# MAIN.net
KiCad netlist of a schematic drawn in Altium Designer
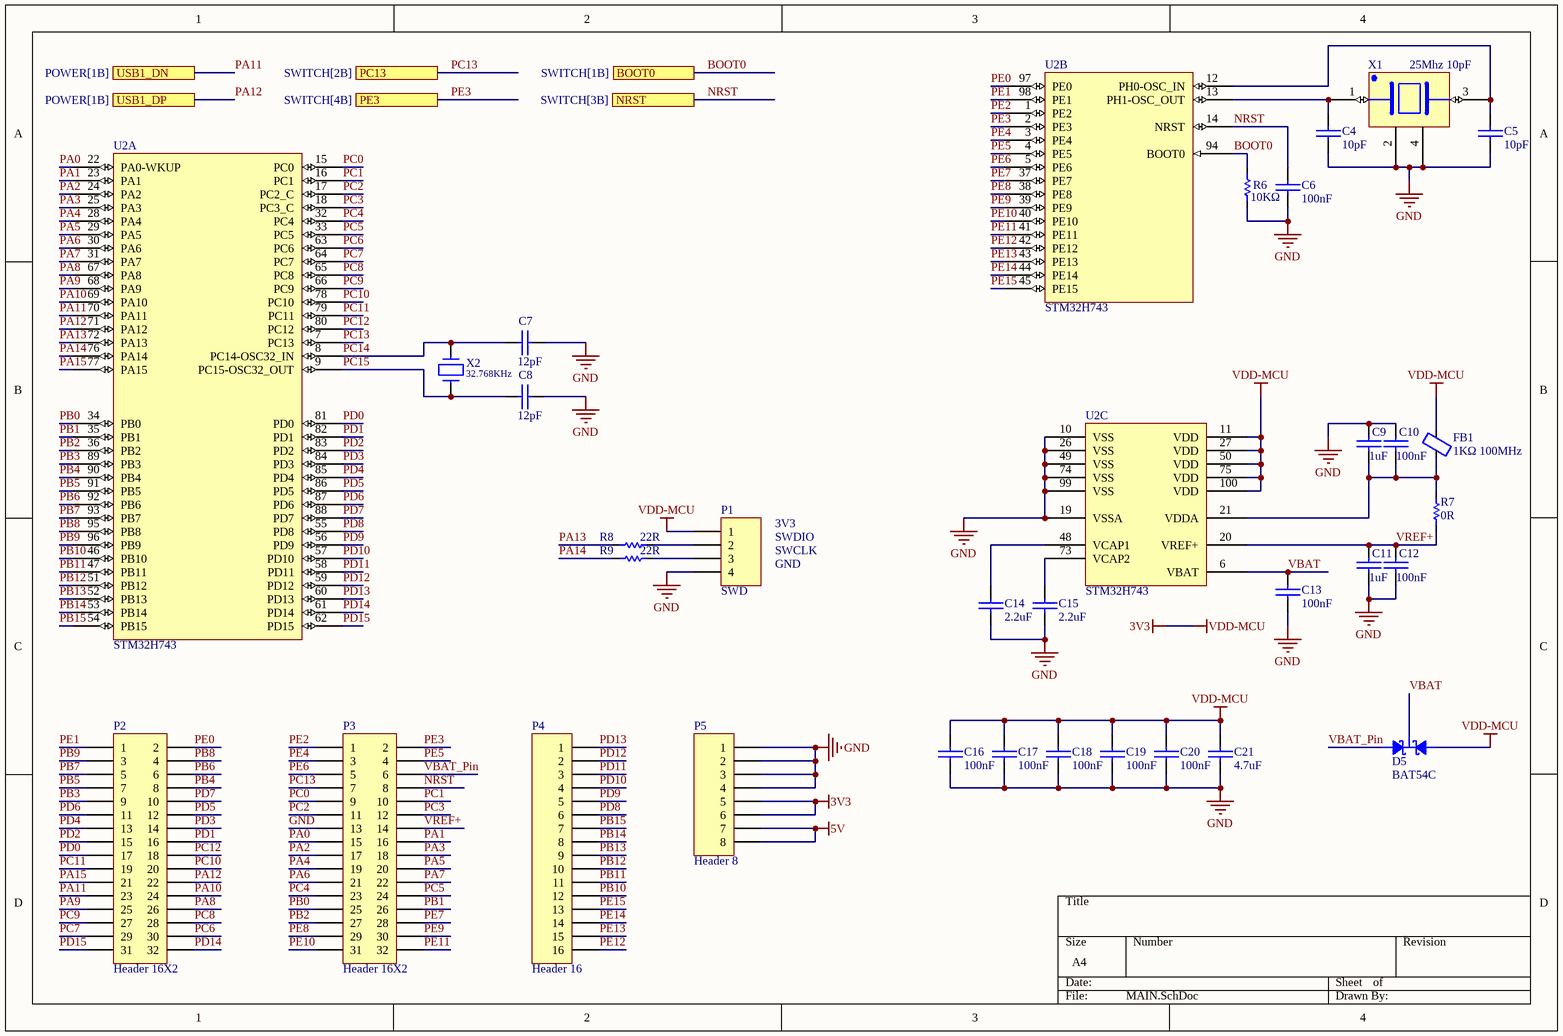
[diagram p0: MAIN.SchDoc]

(export (version "E")
  (design (tool "Eeschema 10.0.6"))
  (components
    (comp (ref "C4")
      (value "10pF")
      (footprint "0402_Capacitor")
      (description "SMDCapacitor")
      (libsource (lib "Miscellaneous Devices-KST") (part "CAP-Chip"))
    )
    (comp (ref "C5")
      (value "10pF")
      (footprint "0402_Capacitor")
      (description "SMDCapacitor")
      (libsource (lib "Miscellaneous Devices-KST") (part "CAP-Chip"))
    )
    (comp (ref "C6")
      (value "100nF")
      (footprint "0402_Capacitor")
      (description "SMDCapacitor")
      (libsource (lib "Miscellaneous Devices-KST") (part "CAP-Chip"))
    )
    (comp (ref "C7")
      (value "12pF")
      (footprint "0402_Capacitor")
      (description "SMDCapacitor")
      (libsource (lib "Miscellaneous Devices-KST") (part "CAP-Chip"))
    )
    (comp (ref "C8")
      (value "12pF")
      (footprint "0402_Capacitor")
      (description "SMDCapacitor")
      (libsource (lib "Miscellaneous Devices-KST") (part "CAP-Chip"))
    )
    (comp (ref "C9")
      (value "1uF")
      (footprint "0402_Capacitor")
      (description "SMDCapacitor")
      (libsource (lib "Miscellaneous Devices-KST") (part "CAP-Chip"))
    )
    (comp (ref "C10")
      (value "100nF")
      (footprint "0402_Capacitor")
      (description "SMDCapacitor")
      (libsource (lib "Miscellaneous Devices-KST") (part "CAP-Chip"))
    )
    (comp (ref "C11")
      (value "1uF")
      (footprint "0402_Capacitor")
      (description "SMDCapacitor")
      (libsource (lib "Miscellaneous Devices-KST") (part "CAP-Chip"))
    )
    (comp (ref "C12")
      (value "100nF")
      (footprint "0402_Capacitor")
      (description "SMDCapacitor")
      (libsource (lib "Miscellaneous Devices-KST") (part "CAP-Chip"))
    )
    (comp (ref "C13")
      (value "100nF")
      (footprint "0402_Capacitor")
      (description "SMDCapacitor")
      (libsource (lib "Miscellaneous Devices-KST") (part "CAP-Chip"))
    )
    (comp (ref "C14")
      (value "2.2uF")
      (footprint "0402_Capacitor")
      (description "SMDCapacitor")
      (libsource (lib "Miscellaneous Devices-KST") (part "CAP-Chip"))
    )
    (comp (ref "C15")
      (value "2.2uF")
      (footprint "0402_Capacitor")
      (description "SMDCapacitor")
      (libsource (lib "Miscellaneous Devices-KST") (part "CAP-Chip"))
    )
    (comp (ref "C16")
      (value "100nF")
      (footprint "0402_Capacitor")
      (description "SMDCapacitor")
      (libsource (lib "Miscellaneous Devices-KST") (part "CAP-Chip"))
    )
    (comp (ref "C17")
      (value "100nF")
      (footprint "0402_Capacitor")
      (description "SMDCapacitor")
      (libsource (lib "Miscellaneous Devices-KST") (part "CAP-Chip"))
    )
    (comp (ref "C18")
      (value "100nF")
      (footprint "0402_Capacitor")
      (description "SMDCapacitor")
      (libsource (lib "Miscellaneous Devices-KST") (part "CAP-Chip"))
    )
    (comp (ref "C19")
      (value "100nF")
      (footprint "0402_Capacitor")
      (description "SMDCapacitor")
      (libsource (lib "Miscellaneous Devices-KST") (part "CAP-Chip"))
    )
    (comp (ref "C20")
      (value "100nF")
      (footprint "0402_Capacitor")
      (description "SMDCapacitor")
      (libsource (lib "Miscellaneous Devices-KST") (part "CAP-Chip"))
    )
    (comp (ref "C21")
      (value "4.7uF")
      (footprint "0402_Capacitor")
      (description "SMDCapacitor")
      (libsource (lib "Miscellaneous Devices-KST") (part "CAP-Chip"))
    )
    (comp (ref "D5") (value "BAT54C") (footprint "SOT23_3L") (libsource (lib "STM32H743") (part "BAT54C")))
    (comp (ref "FB1")
      (value "1KΩ 100MHz")
      (footprint "0603_Ferrite_Bead")
      (libsource (lib "STM32H743") (part "FB1"))
    )
    (comp (ref "P1")
      (value "SWD")
      (footprint "SWD")
      (description "Header, 4-Pin, Right Angle")
      (fields (field (name "PUBLISHER") "Altium Limited"))
      (libsource (lib "Miscellaneous Connectors") (part "Header 4H"))
    )
    (comp (ref "P2")
      (value "Header 16X2")
      (footprint "16x2_Header")
      (description "Header, 16-Pin, Dual row")
      (fields (field (name "PUBLISHER") "Altium Limited"))
      (libsource (lib "Miscellaneous Connectors") (part "Header 16X2"))
    )
    (comp (ref "P3")
      (value "Header 16X2")
      (footprint "16x2_Header")
      (description "Header, 16-Pin, Dual row")
      (fields (field (name "PUBLISHER") "Altium Limited"))
      (libsource (lib "Miscellaneous Connectors") (part "Header 16X2"))
    )
    (comp (ref "P4")
      (value "Header 16")
      (footprint "16x1_Header")
      (description "Header, 16-Pin")
      (fields (field (name "PUBLISHER") "Altium Limited"))
      (libsource (lib "Miscellaneous Connectors") (part "Header 16"))
    )
    (comp (ref "P5")
      (value "Header 8")
      (footprint "8x1_Header")
      (description "Header, 8-Pin")
      (fields (field (name "PUBLISHER") "Altium Limited"))
      (libsource (lib "Miscellaneous Connectors") (part "Header 8"))
    )
    (comp (ref "R6")
      (value "10KΩ")
      (footprint "0402_Resistor")
      (description "Resistor")
      (fields (field (name "PUBLISHER") "Altium Limited"))
      (libsource (lib "Miscellaneous Devices-KST") (part "Res1"))
    )
    (comp (ref "R7")
      (value "0R")
      (footprint "0402_Resistor")
      (description "Resistor")
      (fields (field (name "PUBLISHER") "Altium Limited"))
      (libsource (lib "Miscellaneous Devices-KST") (part "Res1"))
    )
    (comp (ref "R8")
      (value "22R")
      (footprint "0402_Resistor")
      (description "Resistor")
      (fields (field (name "PUBLISHER") "Altium Limited"))
      (libsource (lib "Miscellaneous Devices-KST") (part "Res1"))
    )
    (comp (ref "R9")
      (value "22R")
      (footprint "0402_Resistor")
      (description "Resistor")
      (fields (field (name "PUBLISHER") "Altium Limited"))
      (libsource (lib "Miscellaneous Devices-KST") (part "Res1"))
    )
    (comp (ref "U2")
      (value "STM32H743")
      (footprint "LQFP100Pin")
      (libsource (lib "STM32H743") (part "STM32H743"))
    )
    (comp (ref "X1")
      (value "25Mhz 10pF")
      (footprint "XTAL_25MHz")
      (libsource (lib "2226051_이강민_STM32H743") (part "XTAL_25MHz"))
    )
    (comp (ref "X2")
      (value "32.768KHz")
      (footprint "XTAL_32.768KHz")
      (description "Crystal")
      (libsource (lib "Miscellaneous Devices-KST") (part "CRYSTAL"))
    )
  )
  (nets
    (net (code "1") (name "/BOOT0") (class "Default")
      (node (ref "R6") (pin "2") (pinfunction "2_2") (pintype "passive"))
      (node (ref "U2") (pin "94") (pinfunction "BOOT0_94") (pintype "bidirectional"))
    )
    (net (code "2") (name "/NRST") (class "Default")
      (node (ref "C6") (pin "1") (pinfunction "1_1") (pintype "passive"))
      (node (ref "P3") (pin "8") (pinfunction "8_8") (pintype "passive"))
      (node (ref "U2") (pin "14") (pinfunction "NRST_14") (pintype "bidirectional"))
    )
    (net (code "3") (name "/PA0") (class "Default")
      (node (ref "P3") (pin "15") (pinfunction "15_15") (pintype "passive"))
      (node (ref "U2") (pin "22") (pinfunction "PA0-WKUP_22") (pintype "bidirectional"))
    )
    (net (code "4") (name "/PA1") (class "Default")
      (node (ref "P3") (pin "16") (pinfunction "16_16") (pintype "passive"))
      (node (ref "U2") (pin "23") (pinfunction "PA1_23") (pintype "bidirectional"))
    )
    (net (code "5") (name "/PA2") (class "Default")
      (node (ref "P3") (pin "17") (pinfunction "17_17") (pintype "passive"))
      (node (ref "U2") (pin "24") (pinfunction "PA2_24") (pintype "bidirectional"))
    )
    (net (code "6") (name "/PA3") (class "Default")
      (node (ref "P3") (pin "18") (pinfunction "18_18") (pintype "passive"))
      (node (ref "U2") (pin "25") (pinfunction "PA3_25") (pintype "bidirectional"))
    )
    (net (code "7") (name "/PA4") (class "Default")
      (node (ref "P3") (pin "19") (pinfunction "19_19") (pintype "passive"))
      (node (ref "U2") (pin "28") (pinfunction "PA4_28") (pintype "bidirectional"))
    )
    (net (code "8") (name "/PA5") (class "Default")
      (node (ref "P3") (pin "20") (pinfunction "20_20") (pintype "passive"))
      (node (ref "U2") (pin "29") (pinfunction "PA5_29") (pintype "bidirectional"))
    )
    (net (code "9") (name "/PA6") (class "Default")
      (node (ref "P3") (pin "21") (pinfunction "21_21") (pintype "passive"))
      (node (ref "U2") (pin "30") (pinfunction "PA6_30") (pintype "bidirectional"))
    )
    (net (code "10") (name "/PA7") (class "Default")
      (node (ref "P3") (pin "22") (pinfunction "22_22") (pintype "passive"))
      (node (ref "U2") (pin "31") (pinfunction "PA7_31") (pintype "bidirectional"))
    )
    (net (code "11") (name "/PA8") (class "Default")
      (node (ref "P2") (pin "26") (pinfunction "26_26") (pintype "passive"))
      (node (ref "U2") (pin "67") (pinfunction "PA8_67") (pintype "bidirectional"))
    )
    (net (code "12") (name "/PA9") (class "Default")
      (node (ref "P2") (pin "25") (pinfunction "25_25") (pintype "passive"))
      (node (ref "U2") (pin "68") (pinfunction "PA9_68") (pintype "bidirectional"))
    )
    (net (code "13") (name "/PA10") (class "Default")
      (node (ref "P2") (pin "24") (pinfunction "24_24") (pintype "passive"))
      (node (ref "U2") (pin "69") (pinfunction "PA10_69") (pintype "bidirectional"))
    )
    (net (code "14") (name "/PA11") (class "Default")
      (node (ref "P2") (pin "23") (pinfunction "23_23") (pintype "passive"))
      (node (ref "U2") (pin "70") (pinfunction "PA11_70") (pintype "bidirectional"))
    )
    (net (code "15") (name "/PA12") (class "Default")
      (node (ref "P2") (pin "22") (pinfunction "22_22") (pintype "passive"))
      (node (ref "U2") (pin "71") (pinfunction "PA12_71") (pintype "bidirectional"))
    )
    (net (code "16") (name "/PA13") (class "Default")
      (node (ref "R8") (pin "2") (pinfunction "2_2") (pintype "passive"))
      (node (ref "U2") (pin "72") (pinfunction "PA13_72") (pintype "bidirectional"))
    )
    (net (code "17") (name "/PA14") (class "Default")
      (node (ref "R9") (pin "2") (pinfunction "2_2") (pintype "passive"))
      (node (ref "U2") (pin "76") (pinfunction "PA14_76") (pintype "bidirectional"))
    )
    (net (code "18") (name "/PA15") (class "Default")
      (node (ref "P2") (pin "21") (pinfunction "21_21") (pintype "passive"))
      (node (ref "U2") (pin "77") (pinfunction "PA15_77") (pintype "bidirectional"))
    )
    (net (code "19") (name "/PB0") (class "Default")
      (node (ref "P3") (pin "25") (pinfunction "25_25") (pintype "passive"))
      (node (ref "U2") (pin "34") (pinfunction "PB0_34") (pintype "bidirectional"))
    )
    (net (code "20") (name "/PB1") (class "Default")
      (node (ref "P3") (pin "26") (pinfunction "26_26") (pintype "passive"))
      (node (ref "U2") (pin "35") (pinfunction "PB1_35") (pintype "bidirectional"))
    )
    (net (code "21") (name "/PB2") (class "Default")
      (node (ref "P3") (pin "27") (pinfunction "27_27") (pintype "passive"))
      (node (ref "U2") (pin "36") (pinfunction "PB2_36") (pintype "bidirectional"))
    )
    (net (code "22") (name "/PB3") (class "Default")
      (node (ref "P2") (pin "9") (pinfunction "9_9") (pintype "passive"))
      (node (ref "U2") (pin "89") (pinfunction "PB3_89") (pintype "bidirectional"))
    )
    (net (code "23") (name "/PB4") (class "Default")
      (node (ref "P2") (pin "8") (pinfunction "8_8") (pintype "passive"))
      (node (ref "U2") (pin "90") (pinfunction "PB4_90") (pintype "bidirectional"))
    )
    (net (code "24") (name "/PB5") (class "Default")
      (node (ref "P2") (pin "7") (pinfunction "7_7") (pintype "passive"))
      (node (ref "U2") (pin "91") (pinfunction "PB5_91") (pintype "bidirectional"))
    )
    (net (code "25") (name "/PB6") (class "Default")
      (node (ref "P2") (pin "6") (pinfunction "6_6") (pintype "passive"))
      (node (ref "U2") (pin "92") (pinfunction "PB6_92") (pintype "bidirectional"))
    )
    (net (code "26") (name "/PB7") (class "Default")
      (node (ref "P2") (pin "5") (pinfunction "5_5") (pintype "passive"))
      (node (ref "U2") (pin "93") (pinfunction "PB7_93") (pintype "bidirectional"))
    )
    (net (code "27") (name "/PB8") (class "Default")
      (node (ref "P2") (pin "4") (pinfunction "4_4") (pintype "passive"))
      (node (ref "U2") (pin "95") (pinfunction "PB8_95") (pintype "bidirectional"))
    )
    (net (code "28") (name "/PB9") (class "Default")
      (node (ref "P2") (pin "3") (pinfunction "3_3") (pintype "passive"))
      (node (ref "U2") (pin "96") (pinfunction "PB9_96") (pintype "bidirectional"))
    )
    (net (code "29") (name "/PB10") (class "Default")
      (node (ref "P4") (pin "12") (pinfunction "12_12") (pintype "passive"))
      (node (ref "U2") (pin "46") (pinfunction "PB10_46") (pintype "bidirectional"))
    )
    (net (code "30") (name "/PB11") (class "Default")
      (node (ref "P4") (pin "11") (pinfunction "11_11") (pintype "passive"))
      (node (ref "U2") (pin "47") (pinfunction "PB11_47") (pintype "bidirectional"))
    )
    (net (code "31") (name "/PB12") (class "Default")
      (node (ref "P4") (pin "10") (pinfunction "10_10") (pintype "passive"))
      (node (ref "U2") (pin "51") (pinfunction "PB12_51") (pintype "bidirectional"))
    )
    (net (code "32") (name "/PB13") (class "Default")
      (node (ref "P4") (pin "9") (pinfunction "9_9") (pintype "passive"))
      (node (ref "U2") (pin "52") (pinfunction "PB13_52") (pintype "bidirectional"))
    )
    (net (code "33") (name "/PB14") (class "Default")
      (node (ref "P4") (pin "8") (pinfunction "8_8") (pintype "passive"))
      (node (ref "U2") (pin "53") (pinfunction "PB14_53") (pintype "bidirectional"))
    )
    (net (code "34") (name "/PB15") (class "Default")
      (node (ref "P4") (pin "7") (pinfunction "7_7") (pintype "passive"))
      (node (ref "U2") (pin "54") (pinfunction "PB15_54") (pintype "bidirectional"))
    )
    (net (code "35") (name "/PC0") (class "Default")
      (node (ref "P3") (pin "9") (pinfunction "9_9") (pintype "passive"))
      (node (ref "U2") (pin "15") (pinfunction "PC0_15") (pintype "bidirectional"))
    )
    (net (code "36") (name "/PC1") (class "Default")
      (node (ref "P3") (pin "10") (pinfunction "10_10") (pintype "passive"))
      (node (ref "U2") (pin "16") (pinfunction "PC1_16") (pintype "bidirectional"))
    )
    (net (code "37") (name "/PC2") (class "Default")
      (node (ref "P3") (pin "11") (pinfunction "11_11") (pintype "passive"))
      (node (ref "U2") (pin "17") (pinfunction "PC2_C_17") (pintype "bidirectional"))
    )
    (net (code "38") (name "/PC3") (class "Default")
      (node (ref "P3") (pin "12") (pinfunction "12_12") (pintype "passive"))
      (node (ref "U2") (pin "18") (pinfunction "PC3_C_18") (pintype "bidirectional"))
    )
    (net (code "39") (name "/PC4") (class "Default")
      (node (ref "P3") (pin "23") (pinfunction "23_23") (pintype "passive"))
      (node (ref "U2") (pin "32") (pinfunction "PC4_32") (pintype "bidirectional"))
    )
    (net (code "40") (name "/PC5") (class "Default")
      (node (ref "P3") (pin "24") (pinfunction "24_24") (pintype "passive"))
      (node (ref "U2") (pin "33") (pinfunction "PC5_33") (pintype "bidirectional"))
    )
    (net (code "41") (name "/PC6") (class "Default")
      (node (ref "P2") (pin "30") (pinfunction "30_30") (pintype "passive"))
      (node (ref "U2") (pin "63") (pinfunction "PC6_63") (pintype "bidirectional"))
    )
    (net (code "42") (name "/PC7") (class "Default")
      (node (ref "P2") (pin "29") (pinfunction "29_29") (pintype "passive"))
      (node (ref "U2") (pin "64") (pinfunction "PC7_64") (pintype "bidirectional"))
    )
    (net (code "43") (name "/PC8") (class "Default")
      (node (ref "P2") (pin "28") (pinfunction "28_28") (pintype "passive"))
      (node (ref "U2") (pin "65") (pinfunction "PC8_65") (pintype "bidirectional"))
    )
    (net (code "44") (name "/PC9") (class "Default")
      (node (ref "P2") (pin "27") (pinfunction "27_27") (pintype "passive"))
      (node (ref "U2") (pin "66") (pinfunction "PC9_66") (pintype "bidirectional"))
    )
    (net (code "45") (name "/PC10") (class "Default")
      (node (ref "P2") (pin "20") (pinfunction "20_20") (pintype "passive"))
      (node (ref "U2") (pin "78") (pinfunction "PC10_78") (pintype "bidirectional"))
    )
    (net (code "46") (name "/PC11") (class "Default")
      (node (ref "P2") (pin "19") (pinfunction "19_19") (pintype "passive"))
      (node (ref "U2") (pin "79") (pinfunction "PC11_79") (pintype "bidirectional"))
    )
    (net (code "47") (name "/PC12") (class "Default")
      (node (ref "P2") (pin "18") (pinfunction "18_18") (pintype "passive"))
      (node (ref "U2") (pin "80") (pinfunction "PC12_80") (pintype "bidirectional"))
    )
    (net (code "48") (name "/PC13") (class "Default")
      (node (ref "P3") (pin "7") (pinfunction "7_7") (pintype "passive"))
      (node (ref "U2") (pin "7") (pinfunction "PC13_7") (pintype "bidirectional"))
    )
    (net (code "49") (name "/PC14") (class "Default")
      (node (ref "C7") (pin "1") (pinfunction "1_1") (pintype "passive"))
      (node (ref "U2") (pin "8") (pinfunction "PC14-OSC32_IN_8") (pintype "bidirectional"))
      (node (ref "X2") (pin "2") (pinfunction "2_2") (pintype "passive"))
    )
    (net (code "50") (name "/PC15") (class "Default")
      (node (ref "C8") (pin "1") (pinfunction "1_1") (pintype "passive"))
      (node (ref "U2") (pin "9") (pinfunction "PC15-OSC32_OUT_9") (pintype "bidirectional"))
      (node (ref "X2") (pin "1") (pinfunction "1_1") (pintype "passive"))
    )
    (net (code "51") (name "/PD0") (class "Default")
      (node (ref "P2") (pin "17") (pinfunction "17_17") (pintype "passive"))
      (node (ref "U2") (pin "81") (pinfunction "PD0_81") (pintype "bidirectional"))
    )
    (net (code "52") (name "/PD1") (class "Default")
      (node (ref "P2") (pin "16") (pinfunction "16_16") (pintype "passive"))
      (node (ref "U2") (pin "82") (pinfunction "PD1_82") (pintype "bidirectional"))
    )
    (net (code "53") (name "/PD2") (class "Default")
      (node (ref "P2") (pin "15") (pinfunction "15_15") (pintype "passive"))
      (node (ref "U2") (pin "83") (pinfunction "PD2_83") (pintype "bidirectional"))
    )
    (net (code "54") (name "/PD3") (class "Default")
      (node (ref "P2") (pin "14") (pinfunction "14_14") (pintype "passive"))
      (node (ref "U2") (pin "84") (pinfunction "PD3_84") (pintype "bidirectional"))
    )
    (net (code "55") (name "/PD4") (class "Default")
      (node (ref "P2") (pin "13") (pinfunction "13_13") (pintype "passive"))
      (node (ref "U2") (pin "85") (pinfunction "PD4_85") (pintype "bidirectional"))
    )
    (net (code "56") (name "/PD5") (class "Default")
      (node (ref "P2") (pin "12") (pinfunction "12_12") (pintype "passive"))
      (node (ref "U2") (pin "86") (pinfunction "PD5_86") (pintype "bidirectional"))
    )
    (net (code "57") (name "/PD6") (class "Default")
      (node (ref "P2") (pin "11") (pinfunction "11_11") (pintype "passive"))
      (node (ref "U2") (pin "87") (pinfunction "PD6_87") (pintype "bidirectional"))
    )
    (net (code "58") (name "/PD7") (class "Default")
      (node (ref "P2") (pin "10") (pinfunction "10_10") (pintype "passive"))
      (node (ref "U2") (pin "88") (pinfunction "PD7_88") (pintype "bidirectional"))
    )
    (net (code "59") (name "/PD8") (class "Default")
      (node (ref "P4") (pin "6") (pinfunction "6_6") (pintype "passive"))
      (node (ref "U2") (pin "55") (pinfunction "PD8_55") (pintype "bidirectional"))
    )
    (net (code "60") (name "/PD9") (class "Default")
      (node (ref "P4") (pin "5") (pinfunction "5_5") (pintype "passive"))
      (node (ref "U2") (pin "56") (pinfunction "PD9_56") (pintype "bidirectional"))
    )
    (net (code "61") (name "/PD10") (class "Default")
      (node (ref "P4") (pin "4") (pinfunction "4_4") (pintype "passive"))
      (node (ref "U2") (pin "57") (pinfunction "PD10_57") (pintype "bidirectional"))
    )
    (net (code "62") (name "/PD11") (class "Default")
      (node (ref "P4") (pin "3") (pinfunction "3_3") (pintype "passive"))
      (node (ref "U2") (pin "58") (pinfunction "PD11_58") (pintype "bidirectional"))
    )
    (net (code "63") (name "/PD12") (class "Default")
      (node (ref "P4") (pin "2") (pinfunction "2_2") (pintype "passive"))
      (node (ref "U2") (pin "59") (pinfunction "PD12_59") (pintype "bidirectional"))
    )
    (net (code "64") (name "/PD13") (class "Default")
      (node (ref "P4") (pin "1") (pinfunction "1_1") (pintype "passive"))
      (node (ref "U2") (pin "60") (pinfunction "PD13_60") (pintype "bidirectional"))
    )
    (net (code "65") (name "/PD14") (class "Default")
      (node (ref "P2") (pin "32") (pinfunction "32_32") (pintype "passive"))
      (node (ref "U2") (pin "61") (pinfunction "PD14_61") (pintype "bidirectional"))
    )
    (net (code "66") (name "/PD15") (class "Default")
      (node (ref "P2") (pin "31") (pinfunction "31_31") (pintype "passive"))
      (node (ref "U2") (pin "62") (pinfunction "PD15_62") (pintype "bidirectional"))
    )
    (net (code "67") (name "/PE0") (class "Default")
      (node (ref "P2") (pin "2") (pinfunction "2_2") (pintype "passive"))
      (node (ref "U2") (pin "97") (pinfunction "PE0_97") (pintype "bidirectional"))
    )
    (net (code "68") (name "/PE1") (class "Default")
      (node (ref "P2") (pin "1") (pinfunction "1_1") (pintype "passive"))
      (node (ref "U2") (pin "98") (pinfunction "PE1_98") (pintype "bidirectional"))
    )
    (net (code "69") (name "/PE2") (class "Default")
      (node (ref "P3") (pin "1") (pinfunction "1_1") (pintype "passive"))
      (node (ref "U2") (pin "1") (pinfunction "PE2_1") (pintype "bidirectional"))
    )
    (net (code "70") (name "/PE3") (class "Default")
      (node (ref "P3") (pin "2") (pinfunction "2_2") (pintype "passive"))
      (node (ref "U2") (pin "2") (pinfunction "PE3_2") (pintype "bidirectional"))
    )
    (net (code "71") (name "/PE4") (class "Default")
      (node (ref "P3") (pin "3") (pinfunction "3_3") (pintype "passive"))
      (node (ref "U2") (pin "3") (pinfunction "PE4_3") (pintype "bidirectional"))
    )
    (net (code "72") (name "/PE5") (class "Default")
      (node (ref "P3") (pin "4") (pinfunction "4_4") (pintype "passive"))
      (node (ref "U2") (pin "4") (pinfunction "PE5_4") (pintype "bidirectional"))
    )
    (net (code "73") (name "/PE6") (class "Default")
      (node (ref "P3") (pin "5") (pinfunction "5_5") (pintype "passive"))
      (node (ref "U2") (pin "5") (pinfunction "PE6_5") (pintype "bidirectional"))
    )
    (net (code "74") (name "/PE7") (class "Default")
      (node (ref "P3") (pin "28") (pinfunction "28_28") (pintype "passive"))
      (node (ref "U2") (pin "37") (pinfunction "PE7_37") (pintype "bidirectional"))
    )
    (net (code "75") (name "/PE8") (class "Default")
      (node (ref "P3") (pin "29") (pinfunction "29_29") (pintype "passive"))
      (node (ref "U2") (pin "38") (pinfunction "PE8_38") (pintype "bidirectional"))
    )
    (net (code "76") (name "/PE9") (class "Default")
      (node (ref "P3") (pin "30") (pinfunction "30_30") (pintype "passive"))
      (node (ref "U2") (pin "39") (pinfunction "PE9_39") (pintype "bidirectional"))
    )
    (net (code "77") (name "/PE10") (class "Default")
      (node (ref "P3") (pin "31") (pinfunction "31_31") (pintype "passive"))
      (node (ref "U2") (pin "40") (pinfunction "PE10_40") (pintype "bidirectional"))
    )
    (net (code "78") (name "/PE11") (class "Default")
      (node (ref "P3") (pin "32") (pinfunction "32_32") (pintype "passive"))
      (node (ref "U2") (pin "41") (pinfunction "PE11_41") (pintype "bidirectional"))
    )
    (net (code "79") (name "/PE12") (class "Default")
      (node (ref "P4") (pin "16") (pinfunction "16_16") (pintype "passive"))
      (node (ref "U2") (pin "42") (pinfunction "PE12_42") (pintype "bidirectional"))
    )
    (net (code "80") (name "/PE13") (class "Default")
      (node (ref "P4") (pin "15") (pinfunction "15_15") (pintype "passive"))
      (node (ref "U2") (pin "43") (pinfunction "PE13_43") (pintype "bidirectional"))
    )
    (net (code "81") (name "/PE14") (class "Default")
      (node (ref "P4") (pin "14") (pinfunction "14_14") (pintype "passive"))
      (node (ref "U2") (pin "44") (pinfunction "PE14_44") (pintype "bidirectional"))
    )
    (net (code "82") (name "/PE15") (class "Default")
      (node (ref "P4") (pin "13") (pinfunction "13_13") (pintype "passive"))
      (node (ref "U2") (pin "45") (pinfunction "PE15_45") (pintype "bidirectional"))
    )
    (net (code "83") (name "/VBAT") (class "Default")
      (node (ref "C13") (pin "1") (pinfunction "1_1") (pintype "passive"))
      (node (ref "D5") (pin "3") (pinfunction "3_3") (pintype "passive"))
      (node (ref "U2") (pin "6") (pinfunction "VBAT_6") (pintype "passive"))
    )
    (net (code "84") (name "/VBAT_Pin") (class "Default")
      (node (ref "D5") (pin "1") (pinfunction "1_1") (pintype "passive"))
      (node (ref "P3") (pin "6") (pinfunction "6_6") (pintype "passive"))
    )
    (net (code "85") (name "/VREF+") (class "Default")
      (node (ref "C11") (pin "1") (pinfunction "1_1") (pintype "passive"))
      (node (ref "C12") (pin "1") (pinfunction "1_1") (pintype "passive"))
      (node (ref "P3") (pin "14") (pinfunction "14_14") (pintype "passive"))
      (node (ref "R7") (pin "1") (pinfunction "1_1") (pintype "passive"))
      (node (ref "U2") (pin "20") (pinfunction "VREF+_20") (pintype "passive"))
    )
    (net (code "86") (name "3V3") (class "Default")
      (node (ref "C16") (pin "1") (pinfunction "1_1") (pintype "passive"))
      (node (ref "C17") (pin "1") (pinfunction "1_1") (pintype "passive"))
      (node (ref "C18") (pin "1") (pinfunction "1_1") (pintype "passive"))
      (node (ref "C19") (pin "1") (pinfunction "1_1") (pintype "passive"))
      (node (ref "C20") (pin "1") (pinfunction "1_1") (pintype "passive"))
      (node (ref "C21") (pin "1") (pinfunction "1_1") (pintype "passive"))
      (node (ref "D5") (pin "2") (pinfunction "2_2") (pintype "passive"))
      (node (ref "FB1") (pin "1") (pintype "passive"))
      (node (ref "P1") (pin "1") (pinfunction "1_1") (pintype "passive"))
      (node (ref "P5") (pin "5") (pinfunction "5_5") (pintype "passive"))
      (node (ref "P5") (pin "6") (pinfunction "6_6") (pintype "passive"))
      (node (ref "U2") (pin "100") (pinfunction "VDD_100") (pintype "passive"))
      (node (ref "U2") (pin "11") (pinfunction "VDD_11") (pintype "passive"))
      (node (ref "U2") (pin "27") (pinfunction "VDD_27") (pintype "passive"))
      (node (ref "U2") (pin "50") (pinfunction "VDD_50") (pintype "passive"))
      (node (ref "U2") (pin "75") (pinfunction "VDD_75") (pintype "passive"))
    )
    (net (code "87") (name "5V") (class "Default")
      (node (ref "P5") (pin "7") (pinfunction "7_7") (pintype "passive"))
      (node (ref "P5") (pin "8") (pinfunction "8_8") (pintype "passive"))
    )
    (net (code "88") (name "GND") (class "Default")
      (node (ref "C10") (pin "1") (pinfunction "1_1") (pintype "passive"))
      (node (ref "C11") (pin "2") (pinfunction "2_2") (pintype "passive"))
      (node (ref "C12") (pin "2") (pinfunction "2_2") (pintype "passive"))
      (node (ref "C13") (pin "2") (pinfunction "2_2") (pintype "passive"))
      (node (ref "C14") (pin "2") (pinfunction "2_2") (pintype "passive"))
      (node (ref "C15") (pin "2") (pinfunction "2_2") (pintype "passive"))
      (node (ref "C16") (pin "2") (pinfunction "2_2") (pintype "passive"))
      (node (ref "C17") (pin "2") (pinfunction "2_2") (pintype "passive"))
      (node (ref "C18") (pin "2") (pinfunction "2_2") (pintype "passive"))
      (node (ref "C19") (pin "2") (pinfunction "2_2") (pintype "passive"))
      (node (ref "C20") (pin "2") (pinfunction "2_2") (pintype "passive"))
      (node (ref "C21") (pin "2") (pinfunction "2_2") (pintype "passive"))
      (node (ref "C4") (pin "2") (pinfunction "2_2") (pintype "passive"))
      (node (ref "C5") (pin "2") (pinfunction "2_2") (pintype "passive"))
      (node (ref "C6") (pin "2") (pinfunction "2_2") (pintype "passive"))
      (node (ref "C7") (pin "2") (pinfunction "2_2") (pintype "passive"))
      (node (ref "C8") (pin "2") (pinfunction "2_2") (pintype "passive"))
      (node (ref "C9") (pin "1") (pinfunction "1_1") (pintype "passive"))
      (node (ref "P1") (pin "4") (pinfunction "4_4") (pintype "passive"))
      (node (ref "P3") (pin "13") (pinfunction "13_13") (pintype "passive"))
      (node (ref "P5") (pin "1") (pinfunction "1_1") (pintype "passive"))
      (node (ref "P5") (pin "2") (pinfunction "2_2") (pintype "passive"))
      (node (ref "P5") (pin "3") (pinfunction "3_3") (pintype "passive"))
      (node (ref "P5") (pin "4") (pinfunction "4_4") (pintype "passive"))
      (node (ref "R6") (pin "1") (pinfunction "1_1") (pintype "passive"))
      (node (ref "U2") (pin "10") (pinfunction "VSS_10") (pintype "passive"))
      (node (ref "U2") (pin "19") (pinfunction "VSSA_19") (pintype "passive"))
      (node (ref "U2") (pin "26") (pinfunction "VSS_26") (pintype "passive"))
      (node (ref "U2") (pin "49") (pinfunction "VSS_49") (pintype "passive"))
      (node (ref "U2") (pin "74") (pinfunction "VSS_74") (pintype "passive"))
      (node (ref "U2") (pin "99") (pinfunction "VSS_99") (pintype "passive"))
      (node (ref "X1") (pin "2") (pinfunction "2_2") (pintype "passive"))
      (node (ref "X1") (pin "4") (pinfunction "4_4") (pintype "passive"))
    )
    (net (code "89") (name "Net-(P1-Pad2)") (class "Default")
      (node (ref "P1") (pin "2") (pinfunction "2_2") (pintype "passive"))
      (node (ref "R8") (pin "1") (pinfunction "1_1") (pintype "passive"))
    )
    (net (code "90") (name "Net-(P1-Pad3)") (class "Default")
      (node (ref "P1") (pin "3") (pinfunction "3_3") (pintype "passive"))
      (node (ref "R9") (pin "1") (pinfunction "1_1") (pintype "passive"))
    )
    (net (code "91") (name "Net-(U2B-PH0-OSC_IN)") (class "Default")
      (node (ref "C5") (pin "1") (pinfunction "1_1") (pintype "passive"))
      (node (ref "U2") (pin "12") (pinfunction "PH0-OSC_IN_12") (pintype "bidirectional"))
      (node (ref "X1") (pin "3") (pinfunction "3_3") (pintype "bidirectional"))
    )
    (net (code "92") (name "Net-(U2B-PH1-OSC_OUT)") (class "Default")
      (node (ref "C4") (pin "1") (pinfunction "1_1") (pintype "passive"))
      (node (ref "U2") (pin "13") (pinfunction "PH1-OSC_OUT_13") (pintype "bidirectional"))
      (node (ref "X1") (pin "1") (pinfunction "1_1") (pintype "bidirectional"))
    )
    (net (code "93") (name "Net-(U2C-VCAP1)") (class "Default")
      (node (ref "C14") (pin "1") (pinfunction "1_1") (pintype "passive"))
      (node (ref "U2") (pin "48") (pinfunction "VCAP1_48") (pintype "passive"))
    )
    (net (code "94") (name "Net-(U2C-VCAP2)") (class "Default")
      (node (ref "C15") (pin "1") (pinfunction "1_1") (pintype "passive"))
      (node (ref "U2") (pin "73") (pinfunction "VCAP2_73") (pintype "passive"))
    )
    (net (code "95") (name "Net-(U2C-VDDA)") (class "Default")
      (node (ref "C10") (pin "2") (pinfunction "2_2") (pintype "passive"))
      (node (ref "C9") (pin "2") (pinfunction "2_2") (pintype "passive"))
      (node (ref "FB1") (pin "2") (pintype "passive"))
      (node (ref "R7") (pin "2") (pinfunction "2_2") (pintype "passive"))
      (node (ref "U2") (pin "21") (pinfunction "VDDA_21") (pintype "passive"))
    )
  )
)
